# 2_Out_Headphone_Amp.net
KiCad netlist of a schematic drawn in EAGLE
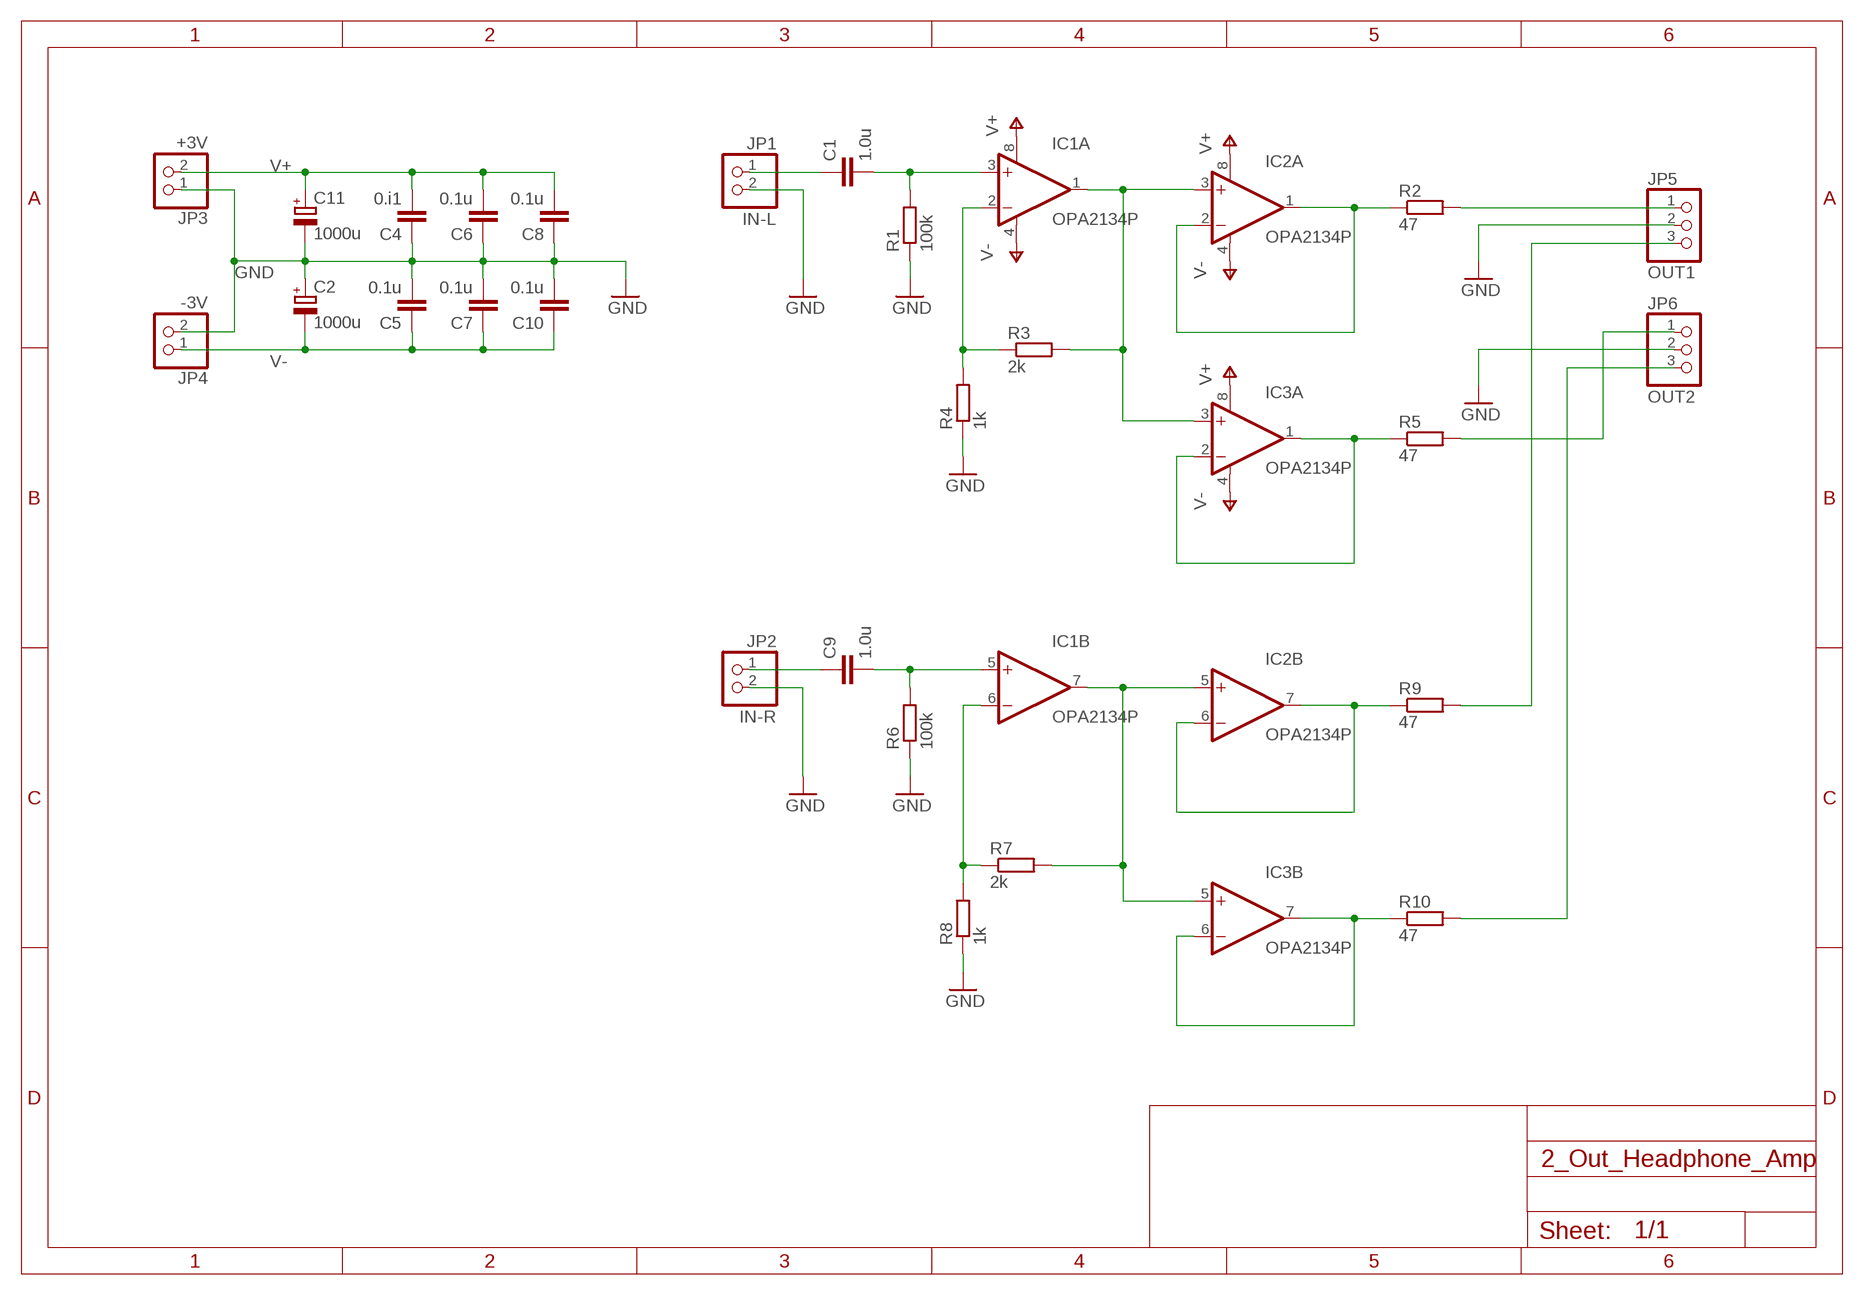
[diagram p0: schematic, sheet 1]

(export (version "E")
  (design (tool "Eeschema 10.0.6"))
  (components
    (comp (ref "C1")
      (value "1.0u")
      (footprint "eagle-import:C050-045X075")
      (libsource (lib "eagle-import") (part "C-EU050-045X075"))
    )
    (comp (ref "C2")
      (value "1000u")
      (footprint "eagle-import:TT5D11L")
      (libsource (lib "eagle-import") (part "CPOL-EUTT5D11L"))
    )
    (comp (ref "C4")
      (value "0.i1")
      (footprint "eagle-import:C050-024X044")
      (libsource (lib "eagle-import") (part "C-EU050-024X044"))
    )
    (comp (ref "C5")
      (value "0.1u")
      (footprint "eagle-import:C050-024X044")
      (libsource (lib "eagle-import") (part "C-EU050-024X044"))
    )
    (comp (ref "C6")
      (value "0.1u")
      (footprint "eagle-import:C050-024X044")
      (libsource (lib "eagle-import") (part "C-EU050-024X044"))
    )
    (comp (ref "C7")
      (value "0.1u")
      (footprint "eagle-import:C050-024X044")
      (libsource (lib "eagle-import") (part "C-EU050-024X044"))
    )
    (comp (ref "C8")
      (value "0.1u")
      (footprint "eagle-import:C050-024X044")
      (libsource (lib "eagle-import") (part "C-EU050-024X044"))
    )
    (comp (ref "C9")
      (value "1.0u")
      (footprint "eagle-import:C050-045X075")
      (libsource (lib "eagle-import") (part "C-EU050-045X075"))
    )
    (comp (ref "C10")
      (value "0.1u")
      (footprint "eagle-import:C050-024X044")
      (libsource (lib "eagle-import") (part "C-EU050-024X044"))
    )
    (comp (ref "C11")
      (value "1000u")
      (footprint "eagle-import:TT5D11L")
      (libsource (lib "eagle-import") (part "CPOL-EUTT5D11L"))
    )
    (comp (ref "IC1")
      (value "OPA2134P")
      (footprint "eagle-import:DIL08")
      (fields (field (name "MF") "TEXAS INSTRUMENTS") (field (name "MPN") "OPA2134PA"))
      (libsource (lib "eagle-import") (part "OPA2134P"))
    )
    (comp (ref "IC2")
      (value "OPA2134P")
      (footprint "eagle-import:DIL08")
      (fields (field (name "MF") "TEXAS INSTRUMENTS") (field (name "MPN") "OPA2134PA"))
      (libsource (lib "eagle-import") (part "OPA2134P"))
    )
    (comp (ref "IC3")
      (value "OPA2134P")
      (footprint "eagle-import:DIL08")
      (fields (field (name "MF") "TEXAS INSTRUMENTS") (field (name "MPN") "OPA2134PA"))
      (libsource (lib "eagle-import") (part "OPA2134P"))
    )
    (comp (ref "JP1")
      (value "IN-L")
      (footprint "eagle-import:1X02")
      (libsource (lib "eagle-import") (part "PINHD-1X2"))
    )
    (comp (ref "JP2")
      (value "IN-R")
      (footprint "eagle-import:1X02")
      (libsource (lib "eagle-import") (part "PINHD-1X2"))
    )
    (comp (ref "JP3")
      (value "+3V")
      (footprint "eagle-import:1X02")
      (libsource (lib "eagle-import") (part "PINHD-1X2"))
    )
    (comp (ref "JP4")
      (value "-3V")
      (footprint "eagle-import:1X02")
      (libsource (lib "eagle-import") (part "PINHD-1X2"))
    )
    (comp (ref "JP5")
      (value "OUT1")
      (footprint "eagle-import:1X03")
      (libsource (lib "eagle-import") (part "PINHD-1X3"))
    )
    (comp (ref "JP6")
      (value "OUT2")
      (footprint "eagle-import:1X03")
      (libsource (lib "eagle-import") (part "PINHD-1X3"))
    )
    (comp (ref "R1")
      (value "100k")
      (footprint "eagle-import:0207_2V")
      (libsource (lib "eagle-import") (part "R-EU_0207/2V"))
    )
    (comp (ref "R2")
      (value "47")
      (footprint "eagle-import:0207_7")
      (libsource (lib "eagle-import") (part "R-EU_0207/7"))
    )
    (comp (ref "R3")
      (value "2k")
      (footprint "eagle-import:0207_7")
      (libsource (lib "eagle-import") (part "R-EU_0207/7"))
    )
    (comp (ref "R4")
      (value "1k")
      (footprint "eagle-import:0207_2V")
      (libsource (lib "eagle-import") (part "R-EU_0207/2V"))
    )
    (comp (ref "R5")
      (value "47")
      (footprint "eagle-import:0207_7")
      (libsource (lib "eagle-import") (part "R-EU_0207/7"))
    )
    (comp (ref "R6")
      (value "100k")
      (footprint "eagle-import:0207_2V")
      (libsource (lib "eagle-import") (part "R-EU_0207/2V"))
    )
    (comp (ref "R7")
      (value "2k")
      (footprint "eagle-import:0207_2V")
      (libsource (lib "eagle-import") (part "R-EU_0207/2V"))
    )
    (comp (ref "R8")
      (value "1k")
      (footprint "eagle-import:0207_2V")
      (libsource (lib "eagle-import") (part "R-EU_0207/2V"))
    )
    (comp (ref "R9")
      (value "47")
      (footprint "eagle-import:0207_7")
      (libsource (lib "eagle-import") (part "R-EU_0207/7"))
    )
    (comp (ref "R10")
      (value "47")
      (footprint "eagle-import:0207_7")
      (libsource (lib "eagle-import") (part "R-EU_0207/7"))
    )
  )
  (nets
    (net (code "1") (name "GND") (class "Default")
      (node (ref "C10") (pin "2") (pinfunction "2_2") (pintype "passive"))
      (node (ref "C11") (pin "-") (pinfunction "-_-") (pintype "passive"))
      (node (ref "C2") (pin "+") (pinfunction "+_+") (pintype "passive"))
      (node (ref "C4") (pin "1") (pinfunction "1_1") (pintype "passive"))
      (node (ref "C5") (pin "2") (pinfunction "2_2") (pintype "passive"))
      (node (ref "C6") (pin "1") (pinfunction "1_1") (pintype "passive"))
      (node (ref "C7") (pin "2") (pinfunction "2_2") (pintype "passive"))
      (node (ref "C8") (pin "1") (pinfunction "1_1") (pintype "passive"))
      (node (ref "JP1") (pin "2") (pinfunction "2_2") (pintype "passive"))
      (node (ref "JP2") (pin "2") (pinfunction "2_2") (pintype "passive"))
      (node (ref "JP3") (pin "1") (pinfunction "1_1") (pintype "passive"))
      (node (ref "JP4") (pin "2") (pinfunction "2_2") (pintype "passive"))
      (node (ref "JP5") (pin "2") (pinfunction "2_2") (pintype "passive"))
      (node (ref "JP6") (pin "2") (pinfunction "2_2") (pintype "passive"))
      (node (ref "R1") (pin "1") (pinfunction "1_1") (pintype "passive"))
      (node (ref "R4") (pin "1") (pinfunction "1_1") (pintype "passive"))
      (node (ref "R6") (pin "1") (pinfunction "1_1") (pintype "passive"))
      (node (ref "R8") (pin "1") (pinfunction "1_1") (pintype "passive"))
    )
    (net (code "2") (name "Net-(C1-Pad1)") (class "Default")
      (node (ref "C1") (pin "1") (pinfunction "1_1") (pintype "passive"))
      (node (ref "JP1") (pin "1") (pinfunction "1_1") (pintype "passive"))
    )
    (net (code "3") (name "Net-(C9-Pad1)") (class "Default")
      (node (ref "C9") (pin "1") (pinfunction "1_1") (pintype "passive"))
      (node (ref "JP2") (pin "1") (pinfunction "1_1") (pintype "passive"))
    )
    (net (code "4") (name "Net-(IC1A-+IN)") (class "Default")
      (node (ref "C1") (pin "2") (pinfunction "2_2") (pintype "passive"))
      (node (ref "IC1") (pin "3") (pinfunction "+IN_3") (pintype "input"))
      (node (ref "R1") (pin "2") (pinfunction "2_2") (pintype "passive"))
    )
    (net (code "5") (name "Net-(IC1A--IN)") (class "Default")
      (node (ref "IC1") (pin "2") (pinfunction "-IN_2") (pintype "input"))
      (node (ref "R3") (pin "1") (pinfunction "1_1") (pintype "passive"))
      (node (ref "R4") (pin "2") (pinfunction "2_2") (pintype "passive"))
    )
    (net (code "6") (name "Net-(IC1A-OUT)") (class "Default")
      (node (ref "IC1") (pin "1") (pinfunction "OUT_1") (pintype "output"))
      (node (ref "IC2") (pin "3") (pinfunction "+IN_3") (pintype "input"))
      (node (ref "IC3") (pin "3") (pinfunction "+IN_3") (pintype "input"))
      (node (ref "R3") (pin "2") (pinfunction "2_2") (pintype "passive"))
    )
    (net (code "7") (name "Net-(IC1B-+IN)") (class "Default")
      (node (ref "C9") (pin "2") (pinfunction "2_2") (pintype "passive"))
      (node (ref "IC1") (pin "5") (pinfunction "+IN_5") (pintype "input"))
      (node (ref "R6") (pin "2") (pinfunction "2_2") (pintype "passive"))
    )
    (net (code "8") (name "Net-(IC1B--IN)") (class "Default")
      (node (ref "IC1") (pin "6") (pinfunction "-IN_6") (pintype "input"))
      (node (ref "R7") (pin "1") (pinfunction "1_1") (pintype "passive"))
      (node (ref "R8") (pin "2") (pinfunction "2_2") (pintype "passive"))
    )
    (net (code "9") (name "Net-(IC1B-OUT)") (class "Default")
      (node (ref "IC1") (pin "7") (pinfunction "OUT_7") (pintype "output"))
      (node (ref "IC2") (pin "5") (pinfunction "+IN_5") (pintype "input"))
      (node (ref "IC3") (pin "5") (pinfunction "+IN_5") (pintype "input"))
      (node (ref "R7") (pin "2") (pinfunction "2_2") (pintype "passive"))
    )
    (net (code "10") (name "Net-(IC2A--IN)") (class "Default")
      (node (ref "IC2") (pin "1") (pinfunction "OUT_1") (pintype "output"))
      (node (ref "IC2") (pin "2") (pinfunction "-IN_2") (pintype "input"))
      (node (ref "R2") (pin "1") (pinfunction "1_1") (pintype "passive"))
    )
    (net (code "11") (name "Net-(IC2B--IN)") (class "Default")
      (node (ref "IC2") (pin "6") (pinfunction "-IN_6") (pintype "input"))
      (node (ref "IC2") (pin "7") (pinfunction "OUT_7") (pintype "output"))
      (node (ref "R9") (pin "1") (pinfunction "1_1") (pintype "passive"))
    )
    (net (code "12") (name "Net-(IC3A--IN)") (class "Default")
      (node (ref "IC3") (pin "1") (pinfunction "OUT_1") (pintype "output"))
      (node (ref "IC3") (pin "2") (pinfunction "-IN_2") (pintype "input"))
      (node (ref "R5") (pin "1") (pinfunction "1_1") (pintype "passive"))
    )
    (net (code "13") (name "Net-(IC3B--IN)") (class "Default")
      (node (ref "IC3") (pin "6") (pinfunction "-IN_6") (pintype "input"))
      (node (ref "IC3") (pin "7") (pinfunction "OUT_7") (pintype "output"))
      (node (ref "R10") (pin "1") (pinfunction "1_1") (pintype "passive"))
    )
    (net (code "14") (name "Net-(JP5-Pad1)") (class "Default")
      (node (ref "JP5") (pin "1") (pinfunction "1_1") (pintype "passive"))
      (node (ref "R2") (pin "2") (pinfunction "2_2") (pintype "passive"))
    )
    (net (code "15") (name "Net-(JP5-Pad3)") (class "Default")
      (node (ref "JP5") (pin "3") (pinfunction "3_3") (pintype "passive"))
      (node (ref "R9") (pin "2") (pinfunction "2_2") (pintype "passive"))
    )
    (net (code "16") (name "Net-(JP6-Pad1)") (class "Default")
      (node (ref "JP6") (pin "1") (pinfunction "1_1") (pintype "passive"))
      (node (ref "R5") (pin "2") (pinfunction "2_2") (pintype "passive"))
    )
    (net (code "17") (name "Net-(JP6-Pad3)") (class "Default")
      (node (ref "JP6") (pin "3") (pinfunction "3_3") (pintype "passive"))
      (node (ref "R10") (pin "2") (pinfunction "2_2") (pintype "passive"))
    )
    (net (code "18") (name "V+") (class "Default")
      (node (ref "C11") (pin "+") (pinfunction "+_+") (pintype "passive"))
      (node (ref "C4") (pin "2") (pinfunction "2_2") (pintype "passive"))
      (node (ref "C6") (pin "2") (pinfunction "2_2") (pintype "passive"))
      (node (ref "C8") (pin "2") (pinfunction "2_2") (pintype "passive"))
      (node (ref "IC1") (pin "8") (pinfunction "V+_8") (pintype "power_in"))
      (node (ref "IC2") (pin "8") (pinfunction "V+_8") (pintype "power_in"))
      (node (ref "IC3") (pin "8") (pinfunction "V+_8") (pintype "power_in"))
      (node (ref "JP3") (pin "2") (pinfunction "2_2") (pintype "passive"))
    )
    (net (code "19") (name "V-") (class "Default")
      (node (ref "C10") (pin "1") (pinfunction "1_1") (pintype "passive"))
      (node (ref "C2") (pin "-") (pinfunction "-_-") (pintype "passive"))
      (node (ref "C5") (pin "1") (pinfunction "1_1") (pintype "passive"))
      (node (ref "C7") (pin "1") (pinfunction "1_1") (pintype "passive"))
      (node (ref "IC1") (pin "4") (pinfunction "V-_4") (pintype "power_in"))
      (node (ref "IC2") (pin "4") (pinfunction "V-_4") (pintype "power_in"))
      (node (ref "IC3") (pin "4") (pinfunction "V-_4") (pintype "power_in"))
      (node (ref "JP4") (pin "1") (pinfunction "1_1") (pintype "passive"))
    )
  )
)
